# LaunchPad_Mini.net
KiCad netlist of a schematic drawn in Altium Designer
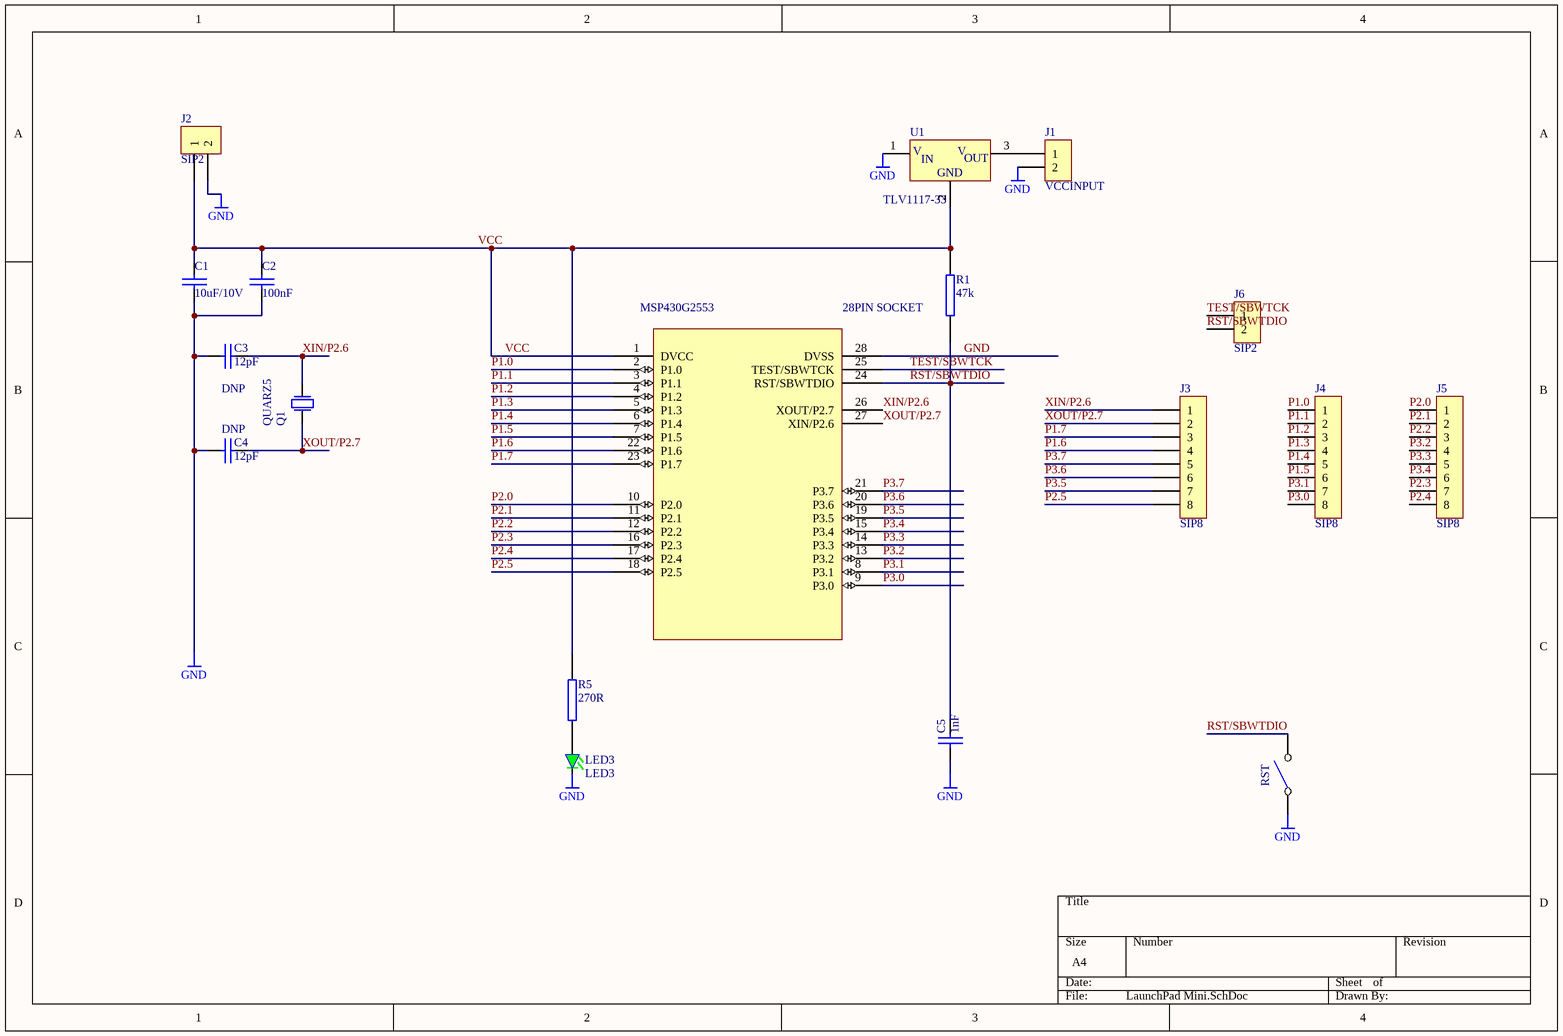
[diagram p0: LaunchPad Mini.SchDoc]

(export (version "E")
  (design (tool "Eeschema 10.0.6"))
  (components
    (comp (ref "C1")
      (value "10uF/10V")
      (footprint "CR2012-0805")
      (description "Capacitor")
      (libsource (lib "*") (part "CAP"))
    )
    (comp (ref "C2")
      (value "100nF")
      (footprint "CR1608-0603")
      (description "Capacitor")
      (libsource (lib "*") (part "CAP"))
    )
    (comp (ref "C3")
      (value "12pF")
      (footprint "CR1608-0603")
      (description "Capacitor")
      (libsource (lib "*") (part "CAP"))
    )
    (comp (ref "C4")
      (value "12pF")
      (footprint "CR1608-0603")
      (description "Capacitor")
      (libsource (lib "*") (part "CAP"))
    )
    (comp (ref "C5")
      (value "1nF")
      (footprint "CR1608-0603")
      (description "Capacitor")
      (libsource (lib "*") (part "CAP"))
    )
    (comp (ref "J1")
      (value "VCCINPUT")
      (footprint "SIP2-2.54")
      (description "jointbar")
      (libsource (lib "") (part "SIP2_1"))
    )
    (comp (ref "J2")
      (value "SIP2")
      (footprint "SIP2-2.54")
      (description "jointbar")
      (libsource (lib "接口与插座") (part "SIP2"))
    )
    (comp (ref "J3")
      (value "SIP8")
      (footprint "SIP8-2.54")
      (description "jointbar")
      (libsource (lib "接口与插座") (part "SIP8"))
    )
    (comp (ref "J4")
      (value "SIP8")
      (footprint "SIP8-2.54")
      (description "jointbar")
      (libsource (lib "接口与插座") (part "SIP8"))
    )
    (comp (ref "J5")
      (value "SIP8")
      (footprint "SIP8-2.54")
      (description "jointbar")
      (libsource (lib "接口与插座") (part "SIP8"))
    )
    (comp (ref "J6")
      (value "SIP2")
      (footprint "SIP2-2.54")
      (description "jointbar")
      (libsource (lib "") (part "SIP2_1"))
    )
    (comp (ref "LED3") (value "LED3") (footprint "CR1608-0603") (libsource (lib "常用2") (part "LED")))
    (comp (ref "MSP430G2553")
      (value "28PIN SOCKET")
      (footprint "TSSOP-28")
      (description "Atmel Microcontroller - Library created by carel..  <www.mpfreezone.com>")
      (libsource (lib "AVR单片机") (part "ATMEGA8_DIP28"))
    )
    (comp (ref "Q1")
      (value "QUARZ5")
      (footprint "CR1608-0603")
      (description "Crystal Oscillator")
      (libsource (lib "*") (part "QUARZ5"))
    )
    (comp (ref "R1") (value "47k") (footprint "CR1608-0603") (libsource (lib "*") (part "RES2")))
    (comp (ref "R5") (value "270R") (footprint "CR1608-0603") (libsource (lib "*") (part "RES2")))
    (comp (ref "RST") (value "~") (footprint "PCBComponent_1") (libsource (lib "*") (part "SW SPST")))
    (comp (ref "U1")
      (value "TLV1117-33")
      (footprint "SOT-223")
      (description "3-Terminal Positive Voltage Regulator")
      (libsource (lib "稳压器件") (part "78L05"))
    )
  )
  (nets
    (net (code "1") (name "/P1.0") (class "Default")
      (node (ref "J4") (pin "1") (pinfunction "1_1") (pintype "passive"))
      (node (ref "MSP430G2553") (pin "2") (pinfunction "P1.0_2") (pintype "bidirectional"))
    )
    (net (code "2") (name "/P1.1") (class "Default")
      (node (ref "J4") (pin "2") (pinfunction "2_2") (pintype "passive"))
      (node (ref "MSP430G2553") (pin "3") (pinfunction "P1.1_3") (pintype "bidirectional"))
    )
    (net (code "3") (name "/P1.2") (class "Default")
      (node (ref "J4") (pin "3") (pinfunction "3_3") (pintype "passive"))
      (node (ref "MSP430G2553") (pin "4") (pinfunction "P1.2_4") (pintype "bidirectional"))
    )
    (net (code "4") (name "/P1.3") (class "Default")
      (node (ref "J4") (pin "4") (pinfunction "4_4") (pintype "passive"))
      (node (ref "MSP430G2553") (pin "5") (pinfunction "P1.3_5") (pintype "bidirectional"))
    )
    (net (code "5") (name "/P1.4") (class "Default")
      (node (ref "J4") (pin "5") (pinfunction "5_5") (pintype "passive"))
      (node (ref "MSP430G2553") (pin "6") (pinfunction "P1.4_6") (pintype "bidirectional"))
    )
    (net (code "6") (name "/P1.5") (class "Default")
      (node (ref "J4") (pin "6") (pinfunction "6_6") (pintype "passive"))
      (node (ref "MSP430G2553") (pin "7") (pinfunction "P1.5_7") (pintype "bidirectional"))
    )
    (net (code "7") (name "/P1.6") (class "Default")
      (node (ref "J3") (pin "4") (pinfunction "4_4") (pintype "passive"))
      (node (ref "MSP430G2553") (pin "22") (pinfunction "P1.6_22") (pintype "bidirectional"))
    )
    (net (code "8") (name "/P1.7") (class "Default")
      (node (ref "J3") (pin "3") (pinfunction "3_3") (pintype "passive"))
      (node (ref "MSP430G2553") (pin "23") (pinfunction "P1.7_23") (pintype "bidirectional"))
    )
    (net (code "9") (name "/P2.0") (class "Default")
      (node (ref "J5") (pin "1") (pinfunction "1_1") (pintype "passive"))
      (node (ref "MSP430G2553") (pin "10") (pinfunction "P2.0_10") (pintype "bidirectional"))
    )
    (net (code "10") (name "/P2.1") (class "Default")
      (node (ref "J5") (pin "2") (pinfunction "2_2") (pintype "passive"))
      (node (ref "MSP430G2553") (pin "11") (pinfunction "P2.1_11") (pintype "bidirectional"))
    )
    (net (code "11") (name "/P2.2") (class "Default")
      (node (ref "J5") (pin "3") (pinfunction "3_3") (pintype "passive"))
      (node (ref "MSP430G2553") (pin "12") (pinfunction "P2.2_12") (pintype "bidirectional"))
    )
    (net (code "12") (name "/P2.3") (class "Default")
      (node (ref "J5") (pin "7") (pinfunction "7_7") (pintype "passive"))
      (node (ref "MSP430G2553") (pin "16") (pinfunction "P2.3_16") (pintype "bidirectional"))
    )
    (net (code "13") (name "/P2.4") (class "Default")
      (node (ref "J5") (pin "8") (pinfunction "8_8") (pintype "passive"))
      (node (ref "MSP430G2553") (pin "17") (pinfunction "P2.4_17") (pintype "bidirectional"))
    )
    (net (code "14") (name "/P2.5") (class "Default")
      (node (ref "J3") (pin "8") (pinfunction "8_8") (pintype "passive"))
      (node (ref "MSP430G2553") (pin "18") (pinfunction "P2.5_18") (pintype "bidirectional"))
    )
    (net (code "15") (name "/P3.0") (class "Default")
      (node (ref "J4") (pin "8") (pinfunction "8_8") (pintype "passive"))
      (node (ref "MSP430G2553") (pin "9") (pinfunction "P3.0_9") (pintype "bidirectional"))
    )
    (net (code "16") (name "/P3.1") (class "Default")
      (node (ref "J4") (pin "7") (pinfunction "7_7") (pintype "passive"))
      (node (ref "MSP430G2553") (pin "8") (pinfunction "P3.1_8") (pintype "bidirectional"))
    )
    (net (code "17") (name "/P3.2") (class "Default")
      (node (ref "J5") (pin "4") (pinfunction "4_4") (pintype "passive"))
      (node (ref "MSP430G2553") (pin "13") (pinfunction "P3.2_13") (pintype "bidirectional"))
    )
    (net (code "18") (name "/P3.3") (class "Default")
      (node (ref "J5") (pin "5") (pinfunction "5_5") (pintype "passive"))
      (node (ref "MSP430G2553") (pin "14") (pinfunction "P3.3_14") (pintype "bidirectional"))
    )
    (net (code "19") (name "/P3.4") (class "Default")
      (node (ref "J5") (pin "6") (pinfunction "6_6") (pintype "passive"))
      (node (ref "MSP430G2553") (pin "15") (pinfunction "P3.4_15") (pintype "bidirectional"))
    )
    (net (code "20") (name "/P3.5") (class "Default")
      (node (ref "J3") (pin "7") (pinfunction "7_7") (pintype "passive"))
      (node (ref "MSP430G2553") (pin "19") (pinfunction "P3.5_19") (pintype "bidirectional"))
    )
    (net (code "21") (name "/P3.6") (class "Default")
      (node (ref "J3") (pin "6") (pinfunction "6_6") (pintype "passive"))
      (node (ref "MSP430G2553") (pin "20") (pinfunction "P3.6_20") (pintype "bidirectional"))
    )
    (net (code "22") (name "/P3.7") (class "Default")
      (node (ref "J3") (pin "5") (pinfunction "5_5") (pintype "passive"))
      (node (ref "MSP430G2553") (pin "21") (pinfunction "P3.7_21") (pintype "bidirectional"))
    )
    (net (code "23") (name "/RST{slash}SBWTDIO") (class "Default")
      (node (ref "C5") (pin "1") (pinfunction "1_1") (pintype "passive"))
      (node (ref "J6") (pin "2") (pinfunction "2_2") (pintype "passive"))
      (node (ref "MSP430G2553") (pin "24") (pinfunction "RST/SBWTDIO_24") (pintype "passive"))
      (node (ref "R1") (pin "1") (pinfunction "1_1") (pintype "passive"))
      (node (ref "RST") (pin "2") (pinfunction "NO_2") (pintype "passive"))
    )
    (net (code "24") (name "/TEST{slash}SBWTCK") (class "Default")
      (node (ref "J6") (pin "1") (pinfunction "1_1") (pintype "passive"))
      (node (ref "MSP430G2553") (pin "25") (pinfunction "TEST/SBWTCK_25") (pintype "passive"))
    )
    (net (code "25") (name "/VCC") (class "Default")
      (node (ref "C1") (pin "2") (pinfunction "2_2") (pintype "passive"))
      (node (ref "C2") (pin "2") (pinfunction "2_2") (pintype "passive"))
      (node (ref "J2") (pin "1") (pinfunction "1_1") (pintype "passive"))
      (node (ref "MSP430G2553") (pin "1") (pinfunction "DVCC_1") (pintype "power_in"))
      (node (ref "R1") (pin "2") (pinfunction "2_2") (pintype "passive"))
      (node (ref "R5") (pin "1") (pinfunction "1_1") (pintype "passive"))
      (node (ref "U1") (pin "2") (pinfunction "GND_2") (pintype "passive"))
    )
    (net (code "26") (name "/XIN{slash}P2.6") (class "Default")
      (node (ref "C3") (pin "2") (pinfunction "2_2") (pintype "passive"))
      (node (ref "J3") (pin "1") (pinfunction "1_1") (pintype "passive"))
      (node (ref "MSP430G2553") (pin "26") (pinfunction "XOUT/P2.7_26") (pintype "passive"))
      (node (ref "Q1") (pin "2") (pinfunction "P2_2") (pintype "passive"))
    )
    (net (code "27") (name "/XOUT{slash}P2.7") (class "Default")
      (node (ref "C4") (pin "2") (pinfunction "2_2") (pintype "passive"))
      (node (ref "J3") (pin "2") (pinfunction "2_2") (pintype "passive"))
      (node (ref "MSP430G2553") (pin "27") (pinfunction "XIN/P2.6_27") (pintype "passive"))
      (node (ref "Q1") (pin "1") (pinfunction "P1_1") (pintype "passive"))
    )
    (net (code "28") (name "GND") (class "Default")
      (node (ref "C1") (pin "1") (pinfunction "1_1") (pintype "passive"))
      (node (ref "C2") (pin "1") (pinfunction "1_1") (pintype "passive"))
      (node (ref "C3") (pin "1") (pinfunction "1_1") (pintype "passive"))
      (node (ref "C4") (pin "1") (pinfunction "1_1") (pintype "passive"))
      (node (ref "C5") (pin "2") (pinfunction "2_2") (pintype "passive"))
      (node (ref "J1") (pin "2") (pinfunction "2_2") (pintype "passive"))
      (node (ref "J2") (pin "2") (pinfunction "2_2") (pintype "passive"))
      (node (ref "LED3") (pin "K") (pinfunction "k_K") (pintype "passive"))
      (node (ref "MSP430G2553") (pin "28") (pinfunction "DVSS_28") (pintype "passive"))
      (node (ref "RST") (pin "1") (pinfunction "COMMON_1") (pintype "passive"))
      (node (ref "U1") (pin "1") (pinfunction "VIN_1") (pintype "passive"))
    )
    (net (code "29") (name "Net-(LED3-a)") (class "Default")
      (node (ref "LED3") (pin "A") (pinfunction "a_A") (pintype "passive"))
      (node (ref "R5") (pin "2") (pinfunction "2_2") (pintype "passive"))
    )
    (net (code "30") (name "Net-(U1-VOUT)") (class "Default")
      (node (ref "J1") (pin "1") (pinfunction "1_1") (pintype "passive"))
      (node (ref "U1") (pin "3") (pinfunction "VOUT_3") (pintype "passive"))
    )
  )
)
